# RS485.net
KiCad netlist of a schematic drawn in Altium Designer
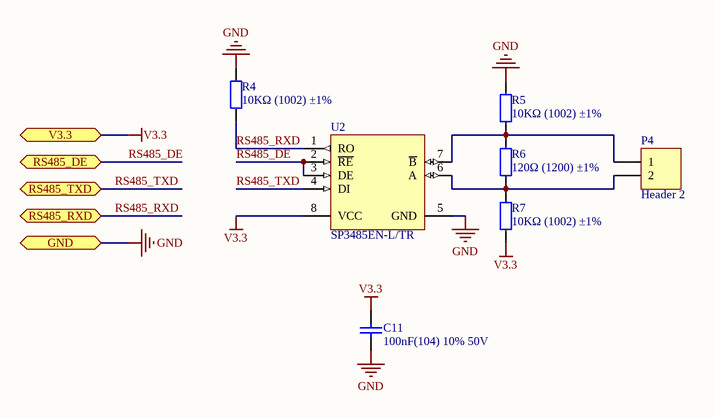
[diagram p0: RS485.SchDoc]

(export (version "E")
  (design (tool "Eeschema 10.0.6"))
  (components
    (comp (ref "C11")
      (value "100nF(104) 10% 50V")
      (footprint "0805_C")
      (description "贴片电容")
      (libsource (lib "Miscellaneous Devices LC") (part "0805 100nF(104) 10% 50V"))
    )
    (comp (ref "P4")
      (value "Header 2")
      (footprint "KF128-2P")
      (description "Header, 2-Pin")
      (fields (field (name "PUBLISHER") "Altium Limited"))
      (libsource (lib "Miscellaneous Connectors") (part "Header 2"))
    )
    (comp (ref "R4")
      (value "10KΩ (1002) ±1%")
      (footprint "0805_R")
      (description "贴片电阻")
      (libsource (lib "Miscellaneous Devices LC") (part "0805 10KΩ (1002) 1%"))
    )
    (comp (ref "R5")
      (value "10KΩ (1002) ±1%")
      (footprint "0805_R")
      (description "贴片电阻")
      (libsource (lib "Miscellaneous Devices LC") (part "0805 10KΩ (1002) 1%"))
    )
    (comp (ref "R6")
      (value "120Ω (1200) ±1%")
      (footprint "0805_R")
      (description "贴片电阻")
      (libsource (lib "Miscellaneous Devices LC") (part "0805 120Ω (1200) 1%"))
    )
    (comp (ref "R7")
      (value "10KΩ (1002) ±1%")
      (footprint "0805_R")
      (description "贴片电阻")
      (libsource (lib "Miscellaneous Devices LC") (part "0805 10KΩ (1002) 1%"))
    )
    (comp (ref "U2")
      (value "SP3485EN-L/TR")
      (footprint "SOIC-8_150mil")
      (description "RS-485/RS-422")
      (libsource (lib "Miscellaneous Devices LC") (part "SP3485EN-L/TR_[C8963]"))
    )
  )
  (nets
    (net (code "1") (name "/RS485_DE") (class "Default")
      (node (ref "U2") (pin "2") (pinfunction "~{RE}_2") (pintype "input"))
      (node (ref "U2") (pin "3") (pinfunction "DE_3") (pintype "input"))
    )
    (net (code "2") (name "/RS485_RXD") (class "Default")
      (node (ref "R4") (pin "1") (pinfunction "1_1") (pintype "passive"))
      (node (ref "U2") (pin "1") (pinfunction "RO_1") (pintype "output"))
    )
    (net (code "3") (name "/RS485_TXD") (class "Default")
      (node (ref "U2") (pin "4") (pinfunction "DI_4") (pintype "input"))
    )
    (net (code "4") (name "GND") (class "Default")
      (node (ref "C11") (pin "2") (pinfunction "2_2") (pintype "passive"))
      (node (ref "R4") (pin "2") (pinfunction "2_2") (pintype "passive"))
      (node (ref "R5") (pin "2") (pinfunction "2_2") (pintype "passive"))
      (node (ref "U2") (pin "5") (pinfunction "GND_5") (pintype "power_in"))
    )
    (net (code "5") (name "Net-(U2-A)") (class "Default")
      (node (ref "P4") (pin "2") (pinfunction "2_2") (pintype "passive"))
      (node (ref "R6") (pin "1") (pinfunction "1_1") (pintype "passive"))
      (node (ref "R7") (pin "2") (pinfunction "2_2") (pintype "passive"))
      (node (ref "U2") (pin "6") (pinfunction "A_6") (pintype "bidirectional"))
    )
    (net (code "6") (name "Net-(U2-~{B})") (class "Default")
      (node (ref "P4") (pin "1") (pinfunction "1_1") (pintype "passive"))
      (node (ref "R5") (pin "1") (pinfunction "1_1") (pintype "passive"))
      (node (ref "R6") (pin "2") (pinfunction "2_2") (pintype "passive"))
      (node (ref "U2") (pin "7") (pinfunction "~{B}_7") (pintype "bidirectional"))
    )
    (net (code "7") (name "V3.3") (class "Default")
      (node (ref "C11") (pin "1") (pinfunction "1_1") (pintype "passive"))
      (node (ref "R7") (pin "1") (pinfunction "1_1") (pintype "passive"))
      (node (ref "U2") (pin "8") (pinfunction "VCC_8") (pintype "power_in"))
    )
  )
)
